# NguyenLyLedThuHongNgoai.net
KiCad netlist of a schematic drawn in Altium Designer
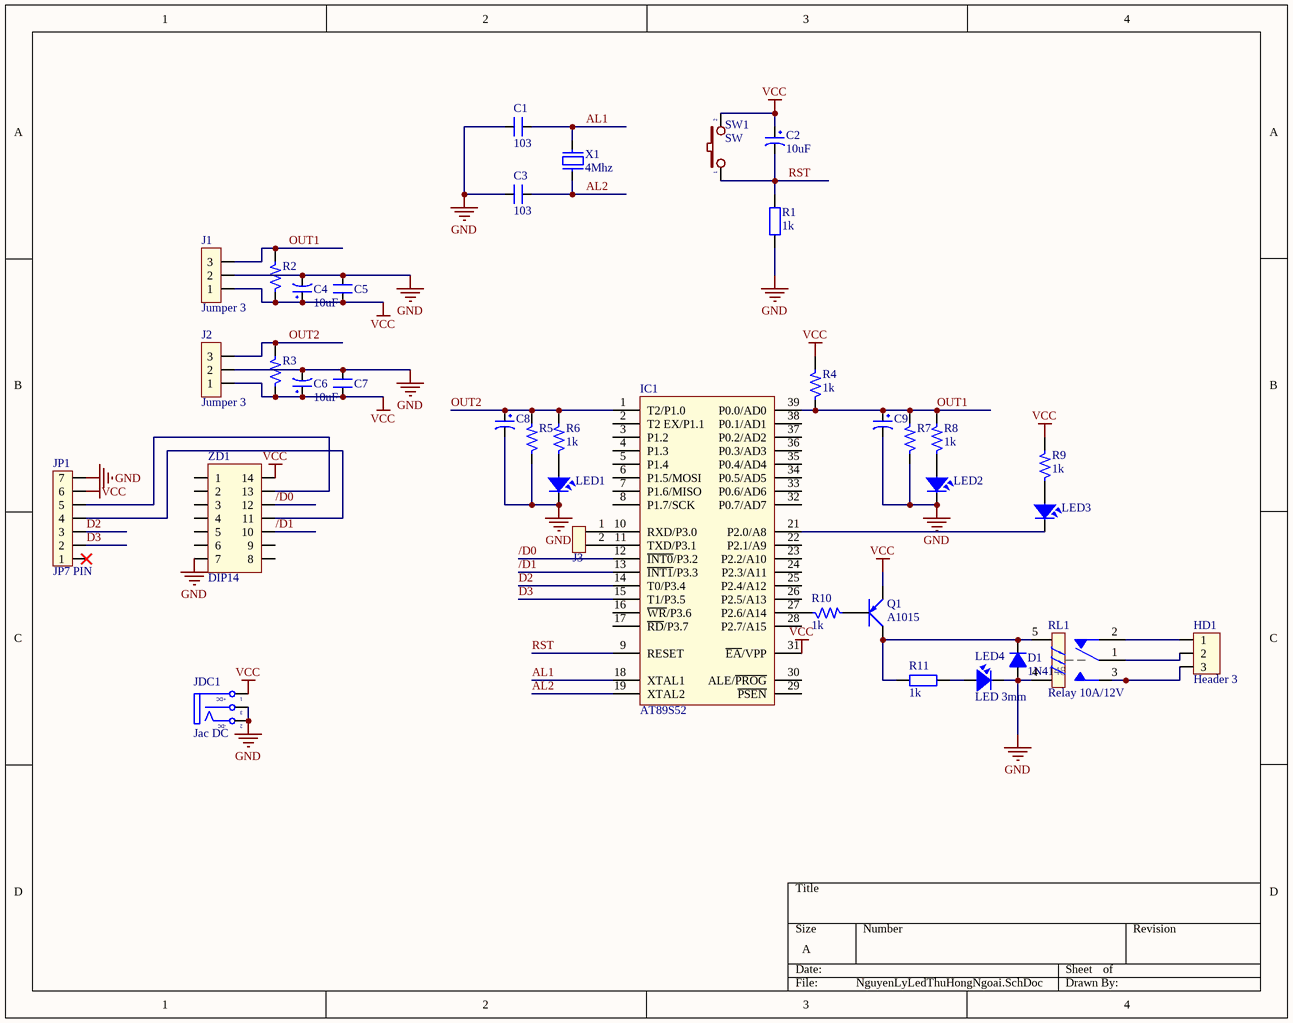
[diagram p0: NguyenLyLedThuHongNgoai.SchDoc]

(export (version "E")
  (design (tool "Eeschema 10.0.6"))
  (components
    (comp (ref "C1")
      (value "103")
      (footprint "CN1.5")
      (description "Cap np 682pF => 104pF")
      (libsource (lib "Tr.Thoai") (part "CN1.5"))
    )
    (comp (ref "C2")
      (value "10uF")
      (footprint "CP1/2")
      (description "Cap P  0,1uF < 22uF , 16 - 50V")
      (libsource (lib "syhaunguyen") (part "CP1"))
    )
    (comp (ref "C3")
      (value "103")
      (footprint "CN1.5")
      (description "Cap np 682pF => 104pF")
      (libsource (lib "Tr.Thoai") (part "CN1.5"))
    )
    (comp (ref "C4")
      (value "10uF")
      (footprint "CP1/2")
      (description "Cap P  0,1uF < 22uF , 16 - 50V")
      (libsource (lib "syhaunguyen") (part "CP1"))
    )
    (comp (ref "C5")
      (value "103")
      (footprint "CN1.5")
      (description "Cap np 682pF => 104pF")
      (libsource (lib "syhaunguyen") (part "CN1.5"))
    )
    (comp (ref "C6")
      (value "10uF")
      (footprint "CP1/2")
      (description "Cap P  0,1uF < 22uF , 16 - 50V")
      (libsource (lib "syhaunguyen") (part "CP1"))
    )
    (comp (ref "C7")
      (value "103")
      (footprint "CN1.5")
      (description "Cap np 682pF => 104pF")
      (libsource (lib "syhaunguyen") (part "CN1.5"))
    )
    (comp (ref "C8")
      (value "10uF")
      (footprint "CP1/2")
      (description "Cap P  0,1uF < 22uF , 16 - 50V")
      (libsource (lib "syhaunguyen") (part "CP1"))
    )
    (comp (ref "C9")
      (value "10uF")
      (footprint "CP1/2")
      (description "Cap P  0,1uF < 22uF , 16 - 50V")
      (libsource (lib "syhaunguyen") (part "CP1"))
    )
    (comp (ref "D1")
      (value "1N4148")
      (footprint "D0.5A")
      (description "1N4148/D 0.5A")
      (libsource (lib "Tr.Thoai") (part "D0.5A"))
    )
    (comp (ref "HD1")
      (value "Header 3")
      (footprint "HED3")
      (description "Header 3 (Green)")
      (libsource (lib "syhaunguyen") (part "Hed3"))
    )
    (comp (ref "IC1")
      (value "AT89S52")
      (footprint "DIP40/W0.6")
      (description "AT89S52, 8k Byte Flash Memory , 40 Pin")
      (libsource (lib "syhaunguyen") (part "AT89S52"))
    )
    (comp (ref "J1") (value "Jumper 3") (footprint "JP3") (libsource (lib "syhaunguyen") (part "JP3")))
    (comp (ref "J2") (value "Jumper 3") (footprint "JP3") (libsource (lib "syhaunguyen") (part "JP3")))
    (comp (ref "J3") (value "Jumper 2") (footprint "JP2") (libsource (lib "Tr.Thoai") (part "JP 2")))
    (comp (ref "JDC1")
      (value "Jac DC")
      (footprint "DC-IN")
      (description "Jac DC input")
      (libsource (lib "Tr.Thoai") (part "JACK DC"))
    )
    (comp (ref "JP1") (value "JP7 PIN") (footprint "JP7") (libsource (lib "syhaunguyen") (part "JP7")))
    (comp (ref "LED1")
      (value "LED")
      (footprint "LED-5TRED")
      (description "LED Single colour Green and Red")
      (libsource (lib "syhaunguyen") (part "LED"))
    )
    (comp (ref "LED2")
      (value "LED")
      (footprint "LED-5TRED")
      (description "LED Single colour Green and Red")
      (libsource (lib "syhaunguyen") (part "LED"))
    )
    (comp (ref "LED3")
      (value "LED")
      (footprint "LED-5TRED")
      (description "LED Single colour Green and Red")
      (libsource (lib "syhaunguyen") (part "LED"))
    )
    (comp (ref "LED4")
      (value "LED 3mm")
      (footprint "LED-5 GRe")
      (description "LED Single colour Green and Red")
      (libsource (lib "Tr.Thoai") (part "LED 3mm"))
    )
    (comp (ref "Q1")
      (value "A1015")
      (footprint "TO-92")
      (description "PNP 600mW, ECB")
      (libsource (lib "Tr.Thoai") (part "A1015"))
    )
    (comp (ref "R1")
      (value "1k")
      (footprint "R1/2W4")
      (description "Resistor 1/4W")
      (libsource (lib "Tr.Thoai") (part "R1/4W"))
    )
    (comp (ref "R2")
      (value "1k")
      (footprint "R1/4W")
      (description "Resistor 1/4W")
      (libsource (lib "syhaunguyen") (part "R"))
    )
    (comp (ref "R3")
      (value "1k")
      (footprint "R1/4W")
      (description "Resistor 1/4W")
      (libsource (lib "syhaunguyen") (part "R"))
    )
    (comp (ref "R4")
      (value "1k")
      (footprint "R1/4W")
      (description "Resistor 1/4W")
      (libsource (lib "syhaunguyen") (part "R"))
    )
    (comp (ref "R5")
      (value "1k")
      (footprint "R1/4W")
      (description "Resistor 1/4W")
      (libsource (lib "syhaunguyen") (part "R"))
    )
    (comp (ref "R6")
      (value "1k")
      (footprint "R1/4W")
      (description "Resistor 1/4W")
      (libsource (lib "syhaunguyen") (part "R"))
    )
    (comp (ref "R7")
      (value "1k")
      (footprint "R1/4W")
      (description "Resistor 1/4W")
      (libsource (lib "syhaunguyen") (part "R"))
    )
    (comp (ref "R8")
      (value "1k")
      (footprint "R1/4W")
      (description "Resistor 1/4W")
      (libsource (lib "syhaunguyen") (part "R"))
    )
    (comp (ref "R9")
      (value "1k")
      (footprint "R1/4W")
      (description "Resistor 1/4W")
      (libsource (lib "syhaunguyen") (part "R"))
    )
    (comp (ref "R10")
      (value "1k")
      (footprint "R1/4W")
      (description "Resistor 1/4W")
      (libsource (lib "syhaunguyen") (part "R"))
    )
    (comp (ref "R11")
      (value "1k")
      (footprint "R1/2W4")
      (description "Resistor 1/4W")
      (libsource (lib "Tr.Thoai") (part "R1/4W"))
    )
    (comp (ref "RL1")
      (value "Relay 10A/12V")
      (footprint "RL_SPDT_10A")
      (description "Relay SPDT,10A - 12VDC 5 Pin")
      (libsource (lib "Tr.Thoai") (part "Relay 1"))
    )
    (comp (ref "SW1")
      (value "SW")
      (footprint "SW2")
      (description "Switch button 2 pin")
      (libsource (lib "Tr.Thoai") (part "SW2"))
    )
    (comp (ref "X1")
      (value "4Mhz")
      (footprint "XT2")
      (description "Crystal For all Crystal 2pin.")
      (libsource (lib "Tr.Thoai") (part "XT2"))
    )
    (comp (ref "ZD1") (value "DIP14") (footprint "DIP14/W0.3") (libsource (lib "syhaunguyen") (part "DIP14")))
  )
  (nets
    (net (code "1") (name "/AL1") (class "Default")
      (node (ref "C1") (pin "2") (pinfunction "2_2") (pintype "passive"))
      (node (ref "IC1") (pin "18") (pinfunction "XTAL1_18") (pintype "passive"))
      (node (ref "X1") (pin "2") (pinfunction "2_2") (pintype "passive"))
    )
    (net (code "2") (name "/AL2") (class "Default")
      (node (ref "C3") (pin "2") (pinfunction "2_2") (pintype "passive"))
      (node (ref "IC1") (pin "19") (pinfunction "XTAL2_19") (pintype "passive"))
      (node (ref "X1") (pin "1") (pinfunction "1_1") (pintype "passive"))
    )
    (net (code "3") (name "/D2") (class "Default")
      (node (ref "IC1") (pin "14") (pinfunction "T0/P3.4_14") (pintype "passive"))
      (node (ref "JP1") (pin "3") (pinfunction "3_3") (pintype "passive"))
    )
    (net (code "4") (name "/D3") (class "Default")
      (node (ref "IC1") (pin "15") (pinfunction "T1/P3.5_15") (pintype "passive"))
      (node (ref "JP1") (pin "2") (pinfunction "2_2") (pintype "passive"))
    )
    (net (code "5") (name "/OUT1") (class "Default")
      (node (ref "C9") (pin "1") (pinfunction "1_1") (pintype "passive"))
      (node (ref "IC1") (pin "39") (pinfunction "P0.0/AD0_39") (pintype "passive"))
      (node (ref "J1") (pin "3") (pinfunction "3_3") (pintype "passive"))
      (node (ref "R2") (pin "2") (pinfunction "2_2") (pintype "passive"))
      (node (ref "R4") (pin "1") (pinfunction "1_1") (pintype "passive"))
      (node (ref "R7") (pin "2") (pinfunction "2_2") (pintype "passive"))
      (node (ref "R8") (pin "2") (pinfunction "2_2") (pintype "passive"))
    )
    (net (code "6") (name "/OUT2") (class "Default")
      (node (ref "C8") (pin "1") (pinfunction "1_1") (pintype "passive"))
      (node (ref "IC1") (pin "1") (pinfunction "T2/P1.0_1") (pintype "passive"))
      (node (ref "J2") (pin "3") (pinfunction "3_3") (pintype "passive"))
      (node (ref "R3") (pin "2") (pinfunction "2_2") (pintype "passive"))
      (node (ref "R5") (pin "2") (pinfunction "2_2") (pintype "passive"))
      (node (ref "R6") (pin "2") (pinfunction "2_2") (pintype "passive"))
    )
    (net (code "7") (name "/RST") (class "Default")
      (node (ref "C2") (pin "2") (pinfunction "2_2") (pintype "passive"))
      (node (ref "IC1") (pin "9") (pinfunction "RESET_9") (pintype "passive"))
      (node (ref "R1") (pin "2") (pinfunction "2_2") (pintype "passive"))
      (node (ref "SW1") (pin "1") (pinfunction "1_1") (pintype "passive"))
    )
    (net (code "8") (name "/{slash}D0") (class "Default")
      (node (ref "IC1") (pin "12") (pinfunction "~{INT0}/P3.2_12") (pintype "passive"))
      (node (ref "ZD1") (pin "12") (pinfunction "12_12") (pintype "passive"))
    )
    (net (code "9") (name "/{slash}D1") (class "Default")
      (node (ref "IC1") (pin "13") (pinfunction "~{INT1}/P3.3_13") (pintype "passive"))
      (node (ref "ZD1") (pin "10") (pinfunction "10_10") (pintype "passive"))
    )
    (net (code "10") (name "GND") (class "Default")
      (node (ref "C1") (pin "1") (pinfunction "1_1") (pintype "passive"))
      (node (ref "C3") (pin "1") (pinfunction "1_1") (pintype "passive"))
      (node (ref "C4") (pin "2") (pinfunction "2_2") (pintype "passive"))
      (node (ref "C5") (pin "1") (pinfunction "1_1") (pintype "passive"))
      (node (ref "C6") (pin "2") (pinfunction "2_2") (pintype "passive"))
      (node (ref "C7") (pin "1") (pinfunction "1_1") (pintype "passive"))
      (node (ref "C8") (pin "2") (pinfunction "2_2") (pintype "passive"))
      (node (ref "C9") (pin "2") (pinfunction "2_2") (pintype "passive"))
      (node (ref "D1") (pin "1") (pinfunction "A_1") (pintype "passive"))
      (node (ref "IC1") (pin "20") (pinfunction "GND_20") (pintype "power_in"))
      (node (ref "J1") (pin "2") (pinfunction "2_2") (pintype "passive"))
      (node (ref "J2") (pin "2") (pinfunction "2_2") (pintype "passive"))
      (node (ref "JDC1") (pin "2") (pinfunction "TN_2") (pintype "passive"))
      (node (ref "JDC1") (pin "3") (pinfunction "S_3") (pintype "power_in"))
      (node (ref "JP1") (pin "7") (pinfunction "7_7") (pintype "passive"))
      (node (ref "LED1") (pin "2") (pinfunction "2_2") (pintype "passive"))
      (node (ref "LED2") (pin "2") (pinfunction "2_2") (pintype "passive"))
      (node (ref "LED4") (pin "2") (pinfunction "2_2") (pintype "passive"))
      (node (ref "R1") (pin "1") (pinfunction "1_1") (pintype "passive"))
      (node (ref "R5") (pin "1") (pinfunction "1_1") (pintype "passive"))
      (node (ref "R7") (pin "1") (pinfunction "1_1") (pintype "passive"))
      (node (ref "RL1") (pin "4") (pinfunction "4_4") (pintype "passive"))
      (node (ref "ZD1") (pin "7") (pinfunction "7_7") (pintype "passive"))
    )
    (net (code "11") (name "Net-(D1-K)") (class "Default")
      (node (ref "D1") (pin "2") (pinfunction "K_2") (pintype "passive"))
      (node (ref "Q1") (pin "2") (pinfunction "C_2") (pintype "passive"))
      (node (ref "R11") (pin "1") (pinfunction "1_1") (pintype "passive"))
      (node (ref "RL1") (pin "5") (pinfunction "5_5") (pintype "passive"))
    )
    (net (code "12") (name "Net-(HD1-Pad1)") (class "Default")
      (node (ref "HD1") (pin "1") (pinfunction "1_1") (pintype "passive"))
      (node (ref "RL1") (pin "2") (pinfunction "2_2") (pintype "passive"))
    )
    (net (code "13") (name "Net-(HD1-Pad2)") (class "Default")
      (node (ref "HD1") (pin "2") (pinfunction "2_2") (pintype "passive"))
      (node (ref "RL1") (pin "1") (pinfunction "1_1") (pintype "passive"))
    )
    (net (code "14") (name "Net-(HD1-Pad3)") (class "Default")
      (node (ref "HD1") (pin "3") (pinfunction "3_3") (pintype "passive"))
      (node (ref "RL1") (pin "3") (pinfunction "3_3") (pintype "passive"))
    )
    (net (code "15") (name "Net-(IC1-P2.0{slash}A8)") (class "Default")
      (node (ref "IC1") (pin "21") (pinfunction "P2.0/A8_21") (pintype "passive"))
      (node (ref "LED3") (pin "2") (pinfunction "2_2") (pintype "passive"))
    )
    (net (code "16") (name "Net-(IC1-P2.6{slash}A14)") (class "Default")
      (node (ref "IC1") (pin "27") (pinfunction "P2.6/A14_27") (pintype "passive"))
      (node (ref "R10") (pin "1") (pinfunction "1_1") (pintype "passive"))
    )
    (net (code "17") (name "Net-(IC1-RXD{slash}P3.0)") (class "Default")
      (node (ref "IC1") (pin "10") (pinfunction "RXD/P3.0_10") (pintype "passive"))
      (node (ref "J3") (pin "1") (pinfunction "1_1") (pintype "passive"))
    )
    (net (code "18") (name "Net-(IC1-TXD{slash}P3.1)") (class "Default")
      (node (ref "IC1") (pin "11") (pinfunction "TXD/P3.1_11") (pintype "passive"))
      (node (ref "J3") (pin "2") (pinfunction "2_2") (pintype "passive"))
    )
    (net (code "19") (name "Net-(JP1-Pad4)") (class "Default")
      (node (ref "JP1") (pin "4") (pinfunction "4_4") (pintype "passive"))
      (node (ref "ZD1") (pin "11") (pinfunction "11_11") (pintype "passive"))
    )
    (net (code "20") (name "Net-(JP1-Pad5)") (class "Default")
      (node (ref "JP1") (pin "5") (pinfunction "5_5") (pintype "passive"))
      (node (ref "ZD1") (pin "13") (pinfunction "13_13") (pintype "passive"))
    )
    (net (code "21") (name "Net-(LED1-Pad1)") (class "Default")
      (node (ref "LED1") (pin "1") (pinfunction "1_1") (pintype "passive"))
      (node (ref "R6") (pin "1") (pinfunction "1_1") (pintype "passive"))
    )
    (net (code "22") (name "Net-(LED2-Pad1)") (class "Default")
      (node (ref "LED2") (pin "1") (pinfunction "1_1") (pintype "passive"))
      (node (ref "R8") (pin "1") (pinfunction "1_1") (pintype "passive"))
    )
    (net (code "23") (name "Net-(LED3-Pad1)") (class "Default")
      (node (ref "LED3") (pin "1") (pinfunction "1_1") (pintype "passive"))
      (node (ref "R9") (pin "1") (pinfunction "1_1") (pintype "passive"))
    )
    (net (code "24") (name "Net-(LED4-Pad1)") (class "Default")
      (node (ref "LED4") (pin "1") (pinfunction "1_1") (pintype "passive"))
      (node (ref "R11") (pin "2") (pinfunction "2_2") (pintype "passive"))
    )
    (net (code "25") (name "Net-(Q1-B)") (class "Default")
      (node (ref "Q1") (pin "3") (pinfunction "B_3") (pintype "passive"))
      (node (ref "R10") (pin "2") (pinfunction "2_2") (pintype "passive"))
    )
    (net (code "26") (name "VCC") (class "Default")
      (node (ref "C2") (pin "1") (pinfunction "1_1") (pintype "passive"))
      (node (ref "C4") (pin "1") (pinfunction "1_1") (pintype "passive"))
      (node (ref "C5") (pin "2") (pinfunction "2_2") (pintype "passive"))
      (node (ref "C6") (pin "1") (pinfunction "1_1") (pintype "passive"))
      (node (ref "C7") (pin "2") (pinfunction "2_2") (pintype "passive"))
      (node (ref "IC1") (pin "31") (pinfunction "~{EA}/VPP_31") (pintype "passive"))
      (node (ref "IC1") (pin "40") (pinfunction "VCC_40") (pintype "power_in"))
      (node (ref "J1") (pin "1") (pinfunction "1_1") (pintype "passive"))
      (node (ref "J2") (pin "1") (pinfunction "1_1") (pintype "passive"))
      (node (ref "JDC1") (pin "1") (pinfunction "T_1") (pintype "passive"))
      (node (ref "JP1") (pin "6") (pinfunction "6_6") (pintype "passive"))
      (node (ref "Q1") (pin "1") (pinfunction "E_1") (pintype "passive"))
      (node (ref "R2") (pin "1") (pinfunction "1_1") (pintype "passive"))
      (node (ref "R3") (pin "1") (pinfunction "1_1") (pintype "passive"))
      (node (ref "R4") (pin "2") (pinfunction "2_2") (pintype "passive"))
      (node (ref "R9") (pin "2") (pinfunction "2_2") (pintype "passive"))
      (node (ref "SW1") (pin "2") (pinfunction "2_2") (pintype "passive"))
      (node (ref "ZD1") (pin "14") (pinfunction "14_14") (pintype "passive"))
    )
    (net (code "27") (name "unconnected-(IC1-ALE{slash}~{PROG}-Pad30)") (class "Default")
      (node (ref "IC1") (pin "30") (pinfunction "ALE/~{PROG}_30") (pintype "passive"))
    )
    (net (code "28") (name "unconnected-(IC1-P0.1{slash}AD1-Pad38)") (class "Default")
      (node (ref "IC1") (pin "38") (pinfunction "P0.1/AD1_38") (pintype "passive"))
    )
    (net (code "29") (name "unconnected-(IC1-P0.2{slash}AD2-Pad37)") (class "Default")
      (node (ref "IC1") (pin "37") (pinfunction "P0.2/AD2_37") (pintype "passive"))
    )
    (net (code "30") (name "unconnected-(IC1-P0.3{slash}AD3-Pad36)") (class "Default")
      (node (ref "IC1") (pin "36") (pinfunction "P0.3/AD3_36") (pintype "passive"))
    )
    (net (code "31") (name "unconnected-(IC1-P0.4{slash}AD4-Pad35)") (class "Default")
      (node (ref "IC1") (pin "35") (pinfunction "P0.4/AD4_35") (pintype "passive"))
    )
    (net (code "32") (name "unconnected-(IC1-P0.5{slash}AD5-Pad34)") (class "Default")
      (node (ref "IC1") (pin "34") (pinfunction "P0.5/AD5_34") (pintype "passive"))
    )
    (net (code "33") (name "unconnected-(IC1-P0.6{slash}AD6-Pad33)") (class "Default")
      (node (ref "IC1") (pin "33") (pinfunction "P0.6/AD6_33") (pintype "passive"))
    )
    (net (code "34") (name "unconnected-(IC1-P0.7{slash}AD7-Pad32)") (class "Default")
      (node (ref "IC1") (pin "32") (pinfunction "P0.7/AD7_32") (pintype "passive"))
    )
    (net (code "35") (name "unconnected-(IC1-P1.2-Pad3)") (class "Default")
      (node (ref "IC1") (pin "3") (pinfunction "P1.2_3") (pintype "passive"))
    )
    (net (code "36") (name "unconnected-(IC1-P1.3-Pad4)") (class "Default")
      (node (ref "IC1") (pin "4") (pinfunction "P1.3_4") (pintype "passive"))
    )
    (net (code "37") (name "unconnected-(IC1-P1.4-Pad5)") (class "Default")
      (node (ref "IC1") (pin "5") (pinfunction "P1.4_5") (pintype "passive"))
    )
    (net (code "38") (name "unconnected-(IC1-P1.5{slash}MOSI-Pad6)") (class "Default")
      (node (ref "IC1") (pin "6") (pinfunction "P1.5/MOSI_6") (pintype "passive"))
    )
    (net (code "39") (name "unconnected-(IC1-P1.6{slash}MISO-Pad7)") (class "Default")
      (node (ref "IC1") (pin "7") (pinfunction "P1.6/MISO_7") (pintype "passive"))
    )
    (net (code "40") (name "unconnected-(IC1-P1.7{slash}SCK-Pad8)") (class "Default")
      (node (ref "IC1") (pin "8") (pinfunction "P1.7/SCK_8") (pintype "passive"))
    )
    (net (code "41") (name "unconnected-(IC1-P2.1{slash}A9-Pad22)") (class "Default")
      (node (ref "IC1") (pin "22") (pinfunction "P2.1/A9_22") (pintype "passive"))
    )
    (net (code "42") (name "unconnected-(IC1-P2.2{slash}A10-Pad23)") (class "Default")
      (node (ref "IC1") (pin "23") (pinfunction "P2.2/A10_23") (pintype "passive"))
    )
    (net (code "43") (name "unconnected-(IC1-P2.3{slash}A11-Pad24)") (class "Default")
      (node (ref "IC1") (pin "24") (pinfunction "P2.3/A11_24") (pintype "passive"))
    )
    (net (code "44") (name "unconnected-(IC1-P2.4{slash}A12-Pad25)") (class "Default")
      (node (ref "IC1") (pin "25") (pinfunction "P2.4/A12_25") (pintype "passive"))
    )
    (net (code "45") (name "unconnected-(IC1-P2.5{slash}A13-Pad26)") (class "Default")
      (node (ref "IC1") (pin "26") (pinfunction "P2.5/A13_26") (pintype "passive"))
    )
    (net (code "46") (name "unconnected-(IC1-P2.7{slash}A15-Pad28)") (class "Default")
      (node (ref "IC1") (pin "28") (pinfunction "P2.7/A15_28") (pintype "passive"))
    )
    (net (code "47") (name "unconnected-(IC1-T2_EX{slash}P1.1-Pad2)") (class "Default")
      (node (ref "IC1") (pin "2") (pinfunction "T2_EX/P1.1_2") (pintype "passive"))
    )
    (net (code "48") (name "unconnected-(IC1-~{PSEN}-Pad29)") (class "Default")
      (node (ref "IC1") (pin "29") (pinfunction "~{PSEN}_29") (pintype "passive"))
    )
    (net (code "49") (name "unconnected-(IC1-~{RD}{slash}P3.7-Pad17)") (class "Default")
      (node (ref "IC1") (pin "17") (pinfunction "~{RD}/P3.7_17") (pintype "passive"))
    )
    (net (code "50") (name "unconnected-(IC1-~{WR}{slash}P3.6-Pad16)") (class "Default")
      (node (ref "IC1") (pin "16") (pinfunction "~{WR}/P3.6_16") (pintype "passive"))
    )
    (net (code "51") (name "unconnected-(JP1-Pad1)") (class "Default")
      (node (ref "JP1") (pin "1") (pinfunction "1_1") (pintype "passive+no_connect"))
    )
    (net (code "52") (name "unconnected-(ZD1-Pad1)") (class "Default")
      (node (ref "ZD1") (pin "1") (pinfunction "1_1") (pintype "passive"))
    )
    (net (code "53") (name "unconnected-(ZD1-Pad2)") (class "Default")
      (node (ref "ZD1") (pin "2") (pinfunction "2_2") (pintype "passive"))
    )
    (net (code "54") (name "unconnected-(ZD1-Pad3)") (class "Default")
      (node (ref "ZD1") (pin "3") (pinfunction "3_3") (pintype "passive"))
    )
    (net (code "55") (name "unconnected-(ZD1-Pad4)") (class "Default")
      (node (ref "ZD1") (pin "4") (pinfunction "4_4") (pintype "passive"))
    )
    (net (code "56") (name "unconnected-(ZD1-Pad5)") (class "Default")
      (node (ref "ZD1") (pin "5") (pinfunction "5_5") (pintype "passive"))
    )
    (net (code "57") (name "unconnected-(ZD1-Pad6)") (class "Default")
      (node (ref "ZD1") (pin "6") (pinfunction "6_6") (pintype "passive"))
    )
    (net (code "58") (name "unconnected-(ZD1-Pad8)") (class "Default")
      (node (ref "ZD1") (pin "8") (pinfunction "8_8") (pintype "passive"))
    )
    (net (code "59") (name "unconnected-(ZD1-Pad9)") (class "Default")
      (node (ref "ZD1") (pin "9") (pinfunction "9_9") (pintype "passive"))
    )
  )
)
